# RS232.net
KiCad netlist of a schematic drawn in Altium Designer
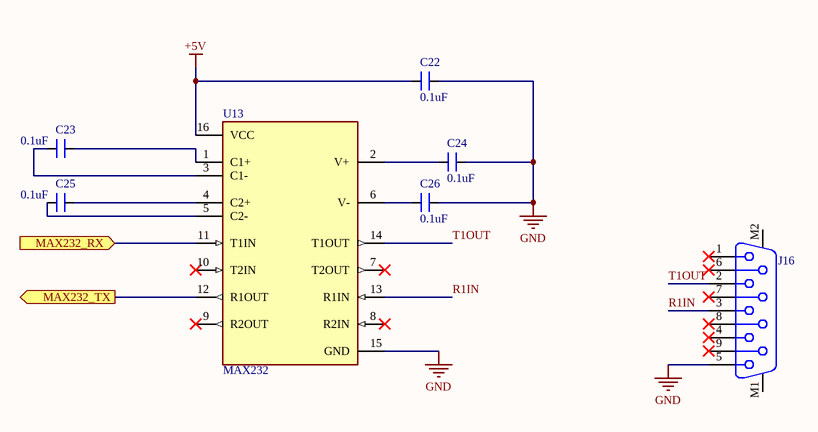
[diagram p0: RS232.SchDoc]

(export (version "E")
  (design (tool "Eeschema 10.0.6"))
  (components
    (comp (ref "C22")
      (value "0.1uF")
      (footprint "CAP_0805")
      (description "0.1µF ±5% 50V Ceramic Capacitor X7R 0805 (2012 Metric)")
      (fields
        (field (name "MANUFACTURER") "AVX Corporation")
        (field (name "MANUFACTURER PART NUMBER") "08055C104JAT4A")
      )
      (libsource (lib "ESTEEMPCBLIB") (part "CAP_0.1uF-50V-5%-0805"))
    )
    (comp (ref "C23")
      (value "0.1uF")
      (footprint "CAP_0805")
      (description "0.1µF ±5% 50V Ceramic Capacitor X7R 0805 (2012 Metric)")
      (fields
        (field (name "MANUFACTURER") "AVX Corporation")
        (field (name "MANUFACTURER PART NUMBER") "08055C104JAT4A")
      )
      (libsource (lib "ESTEEMPCBLIB") (part "CAP_0.1uF-50V-5%-0805"))
    )
    (comp (ref "C24")
      (value "0.1uF")
      (footprint "CAP_0805")
      (description "0.1µF ±5% 50V Ceramic Capacitor X7R 0805 (2012 Metric)")
      (fields
        (field (name "MANUFACTURER") "AVX Corporation")
        (field (name "MANUFACTURER PART NUMBER") "08055C104JAT4A")
      )
      (libsource (lib "ESTEEMPCBLIB") (part "CAP_0.1uF-50V-5%-0805"))
    )
    (comp (ref "C25")
      (value "0.1uF")
      (footprint "CAP_0805")
      (description "0.1µF ±5% 50V Ceramic Capacitor X7R 0805 (2012 Metric)")
      (fields
        (field (name "MANUFACTURER") "AVX Corporation")
        (field (name "MANUFACTURER PART NUMBER") "08055C104JAT4A")
      )
      (libsource (lib "ESTEEMPCBLIB") (part "CAP_0.1uF-50V-5%-0805"))
    )
    (comp (ref "C26")
      (value "0.1uF")
      (footprint "CAP_0805")
      (description "0.1µF ±5% 50V Ceramic Capacitor X7R 0805 (2012 Metric)")
      (fields
        (field (name "MANUFACTURER") "AVX Corporation")
        (field (name "MANUFACTURER PART NUMBER") "08055C104JAT4A")
      )
      (libsource (lib "ESTEEMPCBLIB") (part "CAP_0.1uF-50V-5%-0805"))
    )
    (comp (ref "J16")
      (value "618009231121")
      (footprint "618009231121")
      (description "Female PCB Connector with Hex Screw WR-DSUB, 8.08 mm, Angled, 9 pins")
      (fields (field (name "MANUFACTURER") "Wurth Elektronik") (field (name "PUBLISHER") "WurthElektronik"))
      (libsource (lib "TAREKPCBLIB") (part "DB-9_RIGHT-ANGLE"))
    )
    (comp (ref "U13")
      (value "MAX232")
      (footprint "FP-S16-3-IPC_A")
      (description "IC RS-232 DRVR/RCVR 16-SOIC")
      (fields
        (field (name "OCTOPART") "https://octopart.com/max232cse%2Bt-maxim+integrated-39993384")
        (field (name "MANUFACTURER") "Maxim Integrated")
      )
      (libsource (lib "TAREKPCBLIB") (part "MAX232CSE+T"))
    )
  )
  (nets
    (net (code "1") (name "+5V") (class "Default")
      (node (ref "C22") (pin "2") (pinfunction "2_2") (pintype "passive"))
      (node (ref "U13") (pin "16") (pinfunction "VCC_16") (pintype "power_in"))
    )
    (net (code "2") (name "/MAX232_RX") (class "Default")
      (node (ref "U13") (pin "11") (pinfunction "T1IN_11") (pintype "input"))
    )
    (net (code "3") (name "/MAX232_TX") (class "Default")
      (node (ref "U13") (pin "12") (pinfunction "R1OUT_12") (pintype "output"))
    )
    (net (code "4") (name "/R1IN") (class "Default")
      (node (ref "J16") (pin "3") (pinfunction "3_3") (pintype "passive"))
      (node (ref "U13") (pin "13") (pinfunction "R1IN_13") (pintype "input"))
    )
    (net (code "5") (name "/T1OUT") (class "Default")
      (node (ref "J16") (pin "2") (pinfunction "2_2") (pintype "passive"))
      (node (ref "U13") (pin "14") (pinfunction "T1OUT_14") (pintype "output"))
    )
    (net (code "6") (name "GND") (class "Default")
      (node (ref "C22") (pin "1") (pinfunction "1_1") (pintype "passive"))
      (node (ref "C24") (pin "1") (pinfunction "1_1") (pintype "passive"))
      (node (ref "C26") (pin "1") (pinfunction "1_1") (pintype "passive"))
      (node (ref "J16") (pin "5") (pinfunction "5_5") (pintype "passive"))
      (node (ref "U13") (pin "15") (pinfunction "GND_15") (pintype "power_in"))
    )
    (net (code "7") (name "Net-(U13-C1+)") (class "Default")
      (node (ref "C23") (pin "2") (pinfunction "2_2") (pintype "passive"))
      (node (ref "U13") (pin "1") (pinfunction "C1+_1") (pintype "passive"))
    )
    (net (code "8") (name "Net-(U13-C1-)") (class "Default")
      (node (ref "C23") (pin "1") (pinfunction "1_1") (pintype "passive"))
      (node (ref "U13") (pin "3") (pinfunction "C1-_3") (pintype "passive"))
    )
    (net (code "9") (name "Net-(U13-C2+)") (class "Default")
      (node (ref "C25") (pin "2") (pinfunction "2_2") (pintype "passive"))
      (node (ref "U13") (pin "4") (pinfunction "C2+_4") (pintype "passive"))
    )
    (net (code "10") (name "Net-(U13-C2-)") (class "Default")
      (node (ref "C25") (pin "1") (pinfunction "1_1") (pintype "passive"))
      (node (ref "U13") (pin "5") (pinfunction "C2-_5") (pintype "passive"))
    )
    (net (code "11") (name "Net-(U13-V+)") (class "Default")
      (node (ref "C24") (pin "2") (pinfunction "2_2") (pintype "passive"))
      (node (ref "U13") (pin "2") (pinfunction "V+_2") (pintype "passive"))
    )
    (net (code "12") (name "Net-(U13-V-)") (class "Default")
      (node (ref "C26") (pin "2") (pinfunction "2_2") (pintype "passive"))
      (node (ref "U13") (pin "6") (pinfunction "V-_6") (pintype "passive"))
    )
    (net (code "13") (name "unconnected-(J16-Pad1)") (class "Default")
      (node (ref "J16") (pin "1") (pinfunction "1_1") (pintype "passive+no_connect"))
    )
    (net (code "14") (name "unconnected-(J16-Pad4)") (class "Default")
      (node (ref "J16") (pin "4") (pinfunction "4_4") (pintype "passive+no_connect"))
    )
    (net (code "15") (name "unconnected-(J16-Pad6)") (class "Default")
      (node (ref "J16") (pin "6") (pinfunction "6_6") (pintype "passive+no_connect"))
    )
    (net (code "16") (name "unconnected-(J16-Pad7)") (class "Default")
      (node (ref "J16") (pin "7") (pinfunction "7_7") (pintype "passive+no_connect"))
    )
    (net (code "17") (name "unconnected-(J16-Pad8)") (class "Default")
      (node (ref "J16") (pin "8") (pinfunction "8_8") (pintype "passive+no_connect"))
    )
    (net (code "18") (name "unconnected-(J16-Pad9)") (class "Default")
      (node (ref "J16") (pin "9") (pinfunction "9_9") (pintype "passive+no_connect"))
    )
    (net (code "19") (name "unconnected-(J16-PadM1)") (class "Default")
      (node (ref "J16") (pin "M1") (pinfunction "M1_M1") (pintype "passive"))
    )
    (net (code "20") (name "unconnected-(J16-PadM2)") (class "Default")
      (node (ref "J16") (pin "M2") (pinfunction "M2_M2") (pintype "passive"))
    )
    (net (code "21") (name "unconnected-(U13-R2IN-Pad8)") (class "Default")
      (node (ref "U13") (pin "8") (pinfunction "R2IN_8") (pintype "input+no_connect"))
    )
    (net (code "22") (name "unconnected-(U13-R2OUT-Pad9)") (class "Default")
      (node (ref "U13") (pin "9") (pinfunction "R2OUT_9") (pintype "output+no_connect"))
    )
    (net (code "23") (name "unconnected-(U13-T2IN-Pad10)") (class "Default")
      (node (ref "U13") (pin "10") (pinfunction "T2IN_10") (pintype "input+no_connect"))
    )
    (net (code "24") (name "unconnected-(U13-T2OUT-Pad7)") (class "Default")
      (node (ref "U13") (pin "7") (pinfunction "T2OUT_7") (pintype "output+no_connect"))
    )
  )
)
